# Inputs.net
KiCad netlist of a schematic drawn in Altium Designer
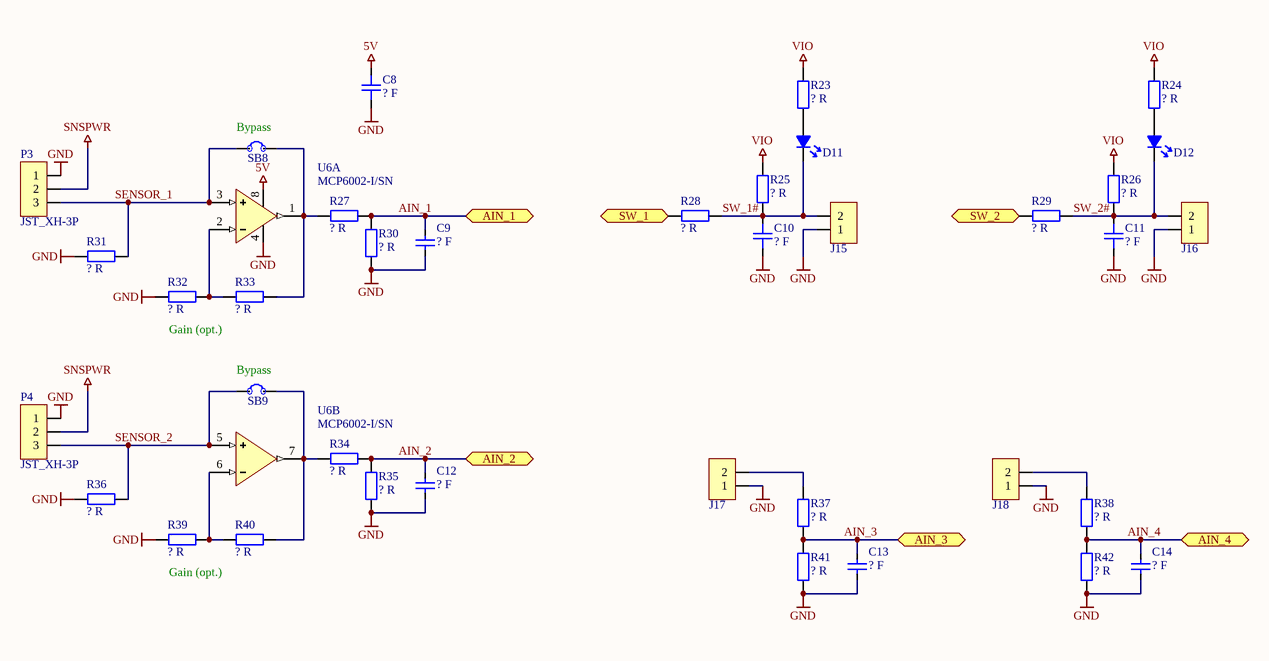
[diagram p0: Inputs.SchDoc]

(export (version "E")
  (design (tool "Eeschema 10.0.6"))
  (components
    (comp (ref "C8")
      (value "? F")
      (footprint "0603C_RF_M")
      (description "Capacitor")
      (fields (field (name "TOLERANCE") "?") (field (name "MANUFACTURER") "Generic Brand"))
      (libsource (lib "") (part "C_1"))
    )
    (comp (ref "C9")
      (value "? F")
      (footprint "0603C_RF_M")
      (description "Capacitor")
      (fields (field (name "TOLERANCE") "?") (field (name "MANUFACTURER") "Generic Brand"))
      (libsource (lib "AG.Generic") (part "C"))
    )
    (comp (ref "C10")
      (value "? F")
      (footprint "0603C_RF_M")
      (description "Capacitor")
      (fields (field (name "TOLERANCE") "?") (field (name "MANUFACTURER") "Generic Brand"))
      (libsource (lib "") (part "C_1"))
    )
    (comp (ref "C11")
      (value "? F")
      (footprint "0603C_RF_M")
      (description "Capacitor")
      (fields (field (name "TOLERANCE") "?") (field (name "MANUFACTURER") "Generic Brand"))
      (libsource (lib "") (part "C_1"))
    )
    (comp (ref "C12")
      (value "? F")
      (footprint "0603C_RF_M")
      (description "Capacitor")
      (fields (field (name "TOLERANCE") "?") (field (name "MANUFACTURER") "Generic Brand"))
      (libsource (lib "AG.Generic") (part "C"))
    )
    (comp (ref "C13")
      (value "? F")
      (footprint "0603C_RF_M")
      (description "Capacitor")
      (fields (field (name "TOLERANCE") "?") (field (name "MANUFACTURER") "Generic Brand"))
      (libsource (lib "AG.Generic") (part "C"))
    )
    (comp (ref "C14")
      (value "? F")
      (footprint "0603C_RF_M")
      (description "Capacitor")
      (fields (field (name "TOLERANCE") "?") (field (name "MANUFACTURER") "Generic Brand"))
      (libsource (lib "AG.Generic") (part "C"))
    )
    (comp (ref "D11")
      (value "Unspecified")
      (footprint "0805LED_RF_M")
      (description "LED")
      (fields (field (name "MANUFACTURER") "Generic Brand"))
      (libsource (lib "AG.Generic") (part "LED"))
    )
    (comp (ref "D12")
      (value "Unspecified")
      (footprint "0805LED_RF_M")
      (description "LED")
      (fields (field (name "MANUFACTURER") "Generic Brand"))
      (libsource (lib "AG.Generic") (part "LED"))
    )
    (comp (ref "J15")
      (value "PINHDR-2P1")
      (footprint "HEADER-2.54-2P1")
      (description "Pin Header Single Row 2 Positions")
      (libsource (lib "AG.Connectors") (part "PINHDR-2P1"))
    )
    (comp (ref "J16")
      (value "PINHDR-2P1")
      (footprint "HEADER-2.54-2P1")
      (description "Pin Header Single Row 2 Positions")
      (libsource (lib "AG.Connectors") (part "PINHDR-2P1"))
    )
    (comp (ref "J17")
      (value "PINHDR-2P1")
      (footprint "HEADER-2.54-2P1")
      (description "Pin Header Single Row 2 Positions")
      (libsource (lib "") (part "PINHDR-2P1_1"))
    )
    (comp (ref "J18")
      (value "PINHDR-2P1")
      (footprint "HEADER-2.54-2P1")
      (description "Pin Header Single Row 2 Positions")
      (libsource (lib "") (part "PINHDR-2P1_1"))
    )
    (comp (ref "P3")
      (value "JST_XH-3P")
      (footprint "AG.Connectors:JST_B3B-XH-A_LF_SN")
      (description "CONN HEADER VERT 3POS 2.5MM")
      (libsource (lib "AG.Connectors") (part "JST_XH-3P"))
    )
    (comp (ref "P4")
      (value "JST_XH-3P")
      (footprint "AG.Connectors:JST_B3B-XH-A_LF_SN")
      (description "CONN HEADER VERT 3POS 2.5MM")
      (libsource (lib "AG.Connectors") (part "JST_XH-3P"))
    )
    (comp (ref "R23")
      (value "? R")
      (footprint "Chip:R0603_RF_M")
      (description "Resistor")
      (fields (field (name "TOLERANCE") "?") (field (name "MANUFACTURER") "Generic Brand"))
      (libsource (lib "AG.Generic") (part "R"))
    )
    (comp (ref "R24")
      (value "? R")
      (footprint "Chip:R0603_RF_M")
      (description "Resistor")
      (fields (field (name "TOLERANCE") "?") (field (name "MANUFACTURER") "Generic Brand"))
      (libsource (lib "AG.Generic") (part "R"))
    )
    (comp (ref "R25")
      (value "? R")
      (footprint "Chip:R0603_RF_M")
      (description "Resistor")
      (fields (field (name "TOLERANCE") "?") (field (name "MANUFACTURER") "Generic Brand"))
      (libsource (lib "AG.Generic") (part "R"))
    )
    (comp (ref "R26")
      (value "? R")
      (footprint "Chip:R0603_RF_M")
      (description "Resistor")
      (fields (field (name "TOLERANCE") "?") (field (name "MANUFACTURER") "Generic Brand"))
      (libsource (lib "AG.Generic") (part "R"))
    )
    (comp (ref "R27")
      (value "? R")
      (footprint "Chip:R0603_RF_M")
      (description "Resistor")
      (fields (field (name "TOLERANCE") "?") (field (name "MANUFACTURER") "Generic Brand"))
      (libsource (lib "AG.Generic") (part "R"))
    )
    (comp (ref "R28")
      (value "? R")
      (footprint "Chip:R0603_RF_M")
      (description "Resistor")
      (fields (field (name "TOLERANCE") "?") (field (name "MANUFACTURER") "Generic Brand"))
      (libsource (lib "AG.Generic") (part "R"))
    )
    (comp (ref "R29")
      (value "? R")
      (footprint "Chip:R0603_RF_M")
      (description "Resistor")
      (fields (field (name "TOLERANCE") "?") (field (name "MANUFACTURER") "Generic Brand"))
      (libsource (lib "AG.Generic") (part "R"))
    )
    (comp (ref "R30")
      (value "? R")
      (footprint "Chip:R0603_RF_M")
      (description "Resistor")
      (fields (field (name "TOLERANCE") "?") (field (name "MANUFACTURER") "Generic Brand"))
      (libsource (lib "AG.Generic") (part "R"))
    )
    (comp (ref "R31")
      (value "? R")
      (footprint "Chip:R0603_RF_M")
      (description "Resistor")
      (fields (field (name "TOLERANCE") "?") (field (name "MANUFACTURER") "Generic Brand"))
      (libsource (lib "AG.Generic") (part "R"))
    )
    (comp (ref "R32")
      (value "? R")
      (footprint "Chip:R0603_RF_M")
      (description "Resistor")
      (fields (field (name "TOLERANCE") "?") (field (name "MANUFACTURER") "Generic Brand"))
      (libsource (lib "AG.Generic") (part "R"))
    )
    (comp (ref "R33")
      (value "? R")
      (footprint "Chip:R0603_RF_M")
      (description "Resistor")
      (fields (field (name "TOLERANCE") "?") (field (name "MANUFACTURER") "Generic Brand"))
      (libsource (lib "AG.Generic") (part "R"))
    )
    (comp (ref "R34")
      (value "? R")
      (footprint "Chip:R0603_RF_M")
      (description "Resistor")
      (fields (field (name "TOLERANCE") "?") (field (name "MANUFACTURER") "Generic Brand"))
      (libsource (lib "AG.Generic") (part "R"))
    )
    (comp (ref "R35")
      (value "? R")
      (footprint "Chip:R0603_RF_M")
      (description "Resistor")
      (fields (field (name "TOLERANCE") "?") (field (name "MANUFACTURER") "Generic Brand"))
      (libsource (lib "AG.Generic") (part "R"))
    )
    (comp (ref "R36")
      (value "? R")
      (footprint "Chip:R0603_RF_M")
      (description "Resistor")
      (fields (field (name "TOLERANCE") "?") (field (name "MANUFACTURER") "Generic Brand"))
      (libsource (lib "AG.Generic") (part "R"))
    )
    (comp (ref "R37")
      (value "? R")
      (footprint "Chip:R0603_RF_M")
      (description "Resistor")
      (fields (field (name "TOLERANCE") "?") (field (name "MANUFACTURER") "Generic Brand"))
      (libsource (lib "AG.Generic") (part "R"))
    )
    (comp (ref "R38")
      (value "? R")
      (footprint "Chip:R0603_RF_M")
      (description "Resistor")
      (fields (field (name "TOLERANCE") "?") (field (name "MANUFACTURER") "Generic Brand"))
      (libsource (lib "AG.Generic") (part "R"))
    )
    (comp (ref "R39")
      (value "? R")
      (footprint "Chip:R0603_RF_M")
      (description "Resistor")
      (fields (field (name "TOLERANCE") "?") (field (name "MANUFACTURER") "Generic Brand"))
      (libsource (lib "AG.Generic") (part "R"))
    )
    (comp (ref "R40")
      (value "? R")
      (footprint "Chip:R0603_RF_M")
      (description "Resistor")
      (fields (field (name "TOLERANCE") "?") (field (name "MANUFACTURER") "Generic Brand"))
      (libsource (lib "AG.Generic") (part "R"))
    )
    (comp (ref "R41")
      (value "? R")
      (footprint "Chip:R0603_RF_M")
      (description "Resistor")
      (fields (field (name "TOLERANCE") "?") (field (name "MANUFACTURER") "Generic Brand"))
      (libsource (lib "AG.Generic") (part "R"))
    )
    (comp (ref "R42")
      (value "? R")
      (footprint "Chip:R0603_RF_M")
      (description "Resistor")
      (fields (field (name "TOLERANCE") "?") (field (name "MANUFACTURER") "Generic Brand"))
      (libsource (lib "AG.Generic") (part "R"))
    )
    (comp (ref "SB8")
      (value "Solder Bridge")
      (footprint "AG.Misc:SLDR_BRDG_0603_OPEN")
      (libsource (lib "AG.Misc") (part "Solder Bridge"))
    )
    (comp (ref "SB9")
      (value "Solder Bridge")
      (footprint "AG.Misc:SLDR_BRDG_0603_OPEN")
      (libsource (lib "AG.Misc") (part "Solder Bridge"))
    )
    (comp (ref "U6")
      (value "MCP6002-I/SN")
      (footprint "AG.IC:SOIC-8")
      (description "IC OPAMP GP 2 CIRCUIT 8SOIC")
      (fields (field (name "DIGIKEY_PART_NO") "MCP6002-I/SN-ND"))
      (libsource (lib "AG.IC") (part "MCP6002-I/SN"))
    )
  )
  (nets
    (net (code "1") (name "/AIN_1") (class "Default")
      (node (ref "C9") (pin "2") (pinfunction "2_2") (pintype "passive"))
      (node (ref "R27") (pin "2") (pintype "passive"))
      (node (ref "R30") (pin "2") (pintype "passive"))
    )
    (net (code "2") (name "/AIN_2") (class "Default")
      (node (ref "C12") (pin "2") (pinfunction "2_2") (pintype "passive"))
      (node (ref "R34") (pin "1") (pintype "passive"))
      (node (ref "R35") (pin "1") (pintype "passive"))
    )
    (net (code "3") (name "/AIN_3") (class "Default")
      (node (ref "C13") (pin "2") (pinfunction "2_2") (pintype "passive"))
      (node (ref "R37") (pin "1") (pintype "passive"))
      (node (ref "R41") (pin "2") (pintype "passive"))
    )
    (net (code "4") (name "/AIN_4") (class "Default")
      (node (ref "C14") (pin "2") (pinfunction "2_2") (pintype "passive"))
      (node (ref "R38") (pin "1") (pintype "passive"))
      (node (ref "R42") (pin "2") (pintype "passive"))
    )
    (net (code "5") (name "/SENSOR_1") (class "Default")
      (node (ref "P3") (pin "3") (pinfunction "3_3") (pintype "passive"))
      (node (ref "R31") (pin "1") (pintype "passive"))
      (node (ref "SB8") (pin "1") (pinfunction "1_1") (pintype "passive"))
      (node (ref "U6") (pin "3") (pintype "input"))
    )
    (net (code "6") (name "/SENSOR_2") (class "Default")
      (node (ref "P4") (pin "3") (pinfunction "3_3") (pintype "passive"))
      (node (ref "R36") (pin "1") (pintype "passive"))
      (node (ref "SB9") (pin "1") (pinfunction "1_1") (pintype "passive"))
      (node (ref "U6") (pin "5") (pintype "input"))
    )
    (net (code "7") (name "/SW_1") (class "Default") (node (ref "R28") (pin "2") (pintype "passive")))
    (net (code "8") (name "/SW_1#") (class "Default")
      (node (ref "C10") (pin "2") (pinfunction "2_2") (pintype "passive"))
      (node (ref "D11") (pin "C") (pinfunction "C_C") (pintype "passive"))
      (node (ref "J15") (pin "2") (pinfunction "2_2") (pintype "passive"))
      (node (ref "R25") (pin "1") (pintype "passive"))
      (node (ref "R28") (pin "1") (pintype "passive"))
    )
    (net (code "9") (name "/SW_2") (class "Default") (node (ref "R29") (pin "2") (pintype "passive")))
    (net (code "10") (name "/SW_2#") (class "Default")
      (node (ref "C11") (pin "2") (pinfunction "2_2") (pintype "passive"))
      (node (ref "D12") (pin "C") (pinfunction "C_C") (pintype "passive"))
      (node (ref "J16") (pin "2") (pinfunction "2_2") (pintype "passive"))
      (node (ref "R26") (pin "1") (pintype "passive"))
      (node (ref "R29") (pin "1") (pintype "passive"))
    )
    (net (code "11") (name "5V") (class "Default")
      (node (ref "C8") (pin "2") (pinfunction "2_2") (pintype "passive"))
      (node (ref "U6") (pin "8") (pintype "power_in"))
    )
    (net (code "12") (name "GND") (class "Default")
      (node (ref "C10") (pin "1") (pinfunction "1_1") (pintype "passive"))
      (node (ref "C11") (pin "1") (pinfunction "1_1") (pintype "passive"))
      (node (ref "C12") (pin "1") (pinfunction "1_1") (pintype "passive"))
      (node (ref "C13") (pin "1") (pinfunction "1_1") (pintype "passive"))
      (node (ref "C14") (pin "1") (pinfunction "1_1") (pintype "passive"))
      (node (ref "C8") (pin "1") (pinfunction "1_1") (pintype "passive"))
      (node (ref "C9") (pin "1") (pinfunction "1_1") (pintype "passive"))
      (node (ref "J15") (pin "1") (pinfunction "1_1") (pintype "passive"))
      (node (ref "J16") (pin "1") (pinfunction "1_1") (pintype "passive"))
      (node (ref "J17") (pin "1") (pinfunction "1_1") (pintype "passive"))
      (node (ref "J18") (pin "1") (pinfunction "1_1") (pintype "passive"))
      (node (ref "P3") (pin "1") (pinfunction "1_1") (pintype "passive"))
      (node (ref "P4") (pin "1") (pinfunction "1_1") (pintype "passive"))
      (node (ref "R30") (pin "1") (pintype "passive"))
      (node (ref "R31") (pin "2") (pintype "passive"))
      (node (ref "R32") (pin "2") (pintype "passive"))
      (node (ref "R35") (pin "2") (pintype "passive"))
      (node (ref "R36") (pin "2") (pintype "passive"))
      (node (ref "R39") (pin "2") (pintype "passive"))
      (node (ref "R41") (pin "1") (pintype "passive"))
      (node (ref "R42") (pin "1") (pintype "passive"))
      (node (ref "U6") (pin "4") (pintype "power_in"))
    )
    (net (code "13") (name "Net-(D11-PadA)") (class "Default")
      (node (ref "D11") (pin "A") (pinfunction "A_A") (pintype "passive"))
      (node (ref "R23") (pin "2") (pintype "passive"))
    )
    (net (code "14") (name "Net-(D12-PadA)") (class "Default")
      (node (ref "D12") (pin "A") (pinfunction "A_A") (pintype "passive"))
      (node (ref "R24") (pin "2") (pintype "passive"))
    )
    (net (code "15") (name "Net-(J17-Pad2)") (class "Default")
      (node (ref "J17") (pin "2") (pinfunction "2_2") (pintype "passive"))
      (node (ref "R37") (pin "2") (pintype "passive"))
    )
    (net (code "16") (name "Net-(J18-Pad2)") (class "Default")
      (node (ref "J18") (pin "2") (pinfunction "2_2") (pintype "passive"))
      (node (ref "R38") (pin "2") (pintype "passive"))
    )
    (net (code "17") (name "Net-(R27-Pad1)") (class "Default")
      (node (ref "R27") (pin "1") (pintype "passive"))
      (node (ref "R33") (pin "1") (pintype "passive"))
      (node (ref "SB8") (pin "2") (pinfunction "2_2") (pintype "passive"))
      (node (ref "U6") (pin "1") (pintype "output"))
    )
    (net (code "18") (name "Net-(R32-Pad1)") (class "Default")
      (node (ref "R32") (pin "1") (pintype "passive"))
      (node (ref "R33") (pin "2") (pintype "passive"))
      (node (ref "U6") (pin "2") (pintype "input"))
    )
    (net (code "19") (name "Net-(R34-Pad2)") (class "Default")
      (node (ref "R34") (pin "2") (pintype "passive"))
      (node (ref "R40") (pin "1") (pintype "passive"))
      (node (ref "SB9") (pin "2") (pinfunction "2_2") (pintype "passive"))
      (node (ref "U6") (pin "7") (pintype "output"))
    )
    (net (code "20") (name "Net-(R39-Pad1)") (class "Default")
      (node (ref "R39") (pin "1") (pintype "passive"))
      (node (ref "R40") (pin "2") (pintype "passive"))
      (node (ref "U6") (pin "6") (pintype "input"))
    )
    (net (code "21") (name "SNSPWR") (class "Default")
      (node (ref "P3") (pin "2") (pinfunction "2_2") (pintype "passive"))
      (node (ref "P4") (pin "2") (pinfunction "2_2") (pintype "passive"))
    )
    (net (code "22") (name "VIO") (class "Default")
      (node (ref "R23") (pin "1") (pintype "passive"))
      (node (ref "R24") (pin "1") (pintype "passive"))
      (node (ref "R25") (pin "2") (pintype "passive"))
      (node (ref "R26") (pin "2") (pintype "passive"))
    )
  )
)
